# decoder_bard.net
KiCad netlist of a schematic drawn in EAGLE
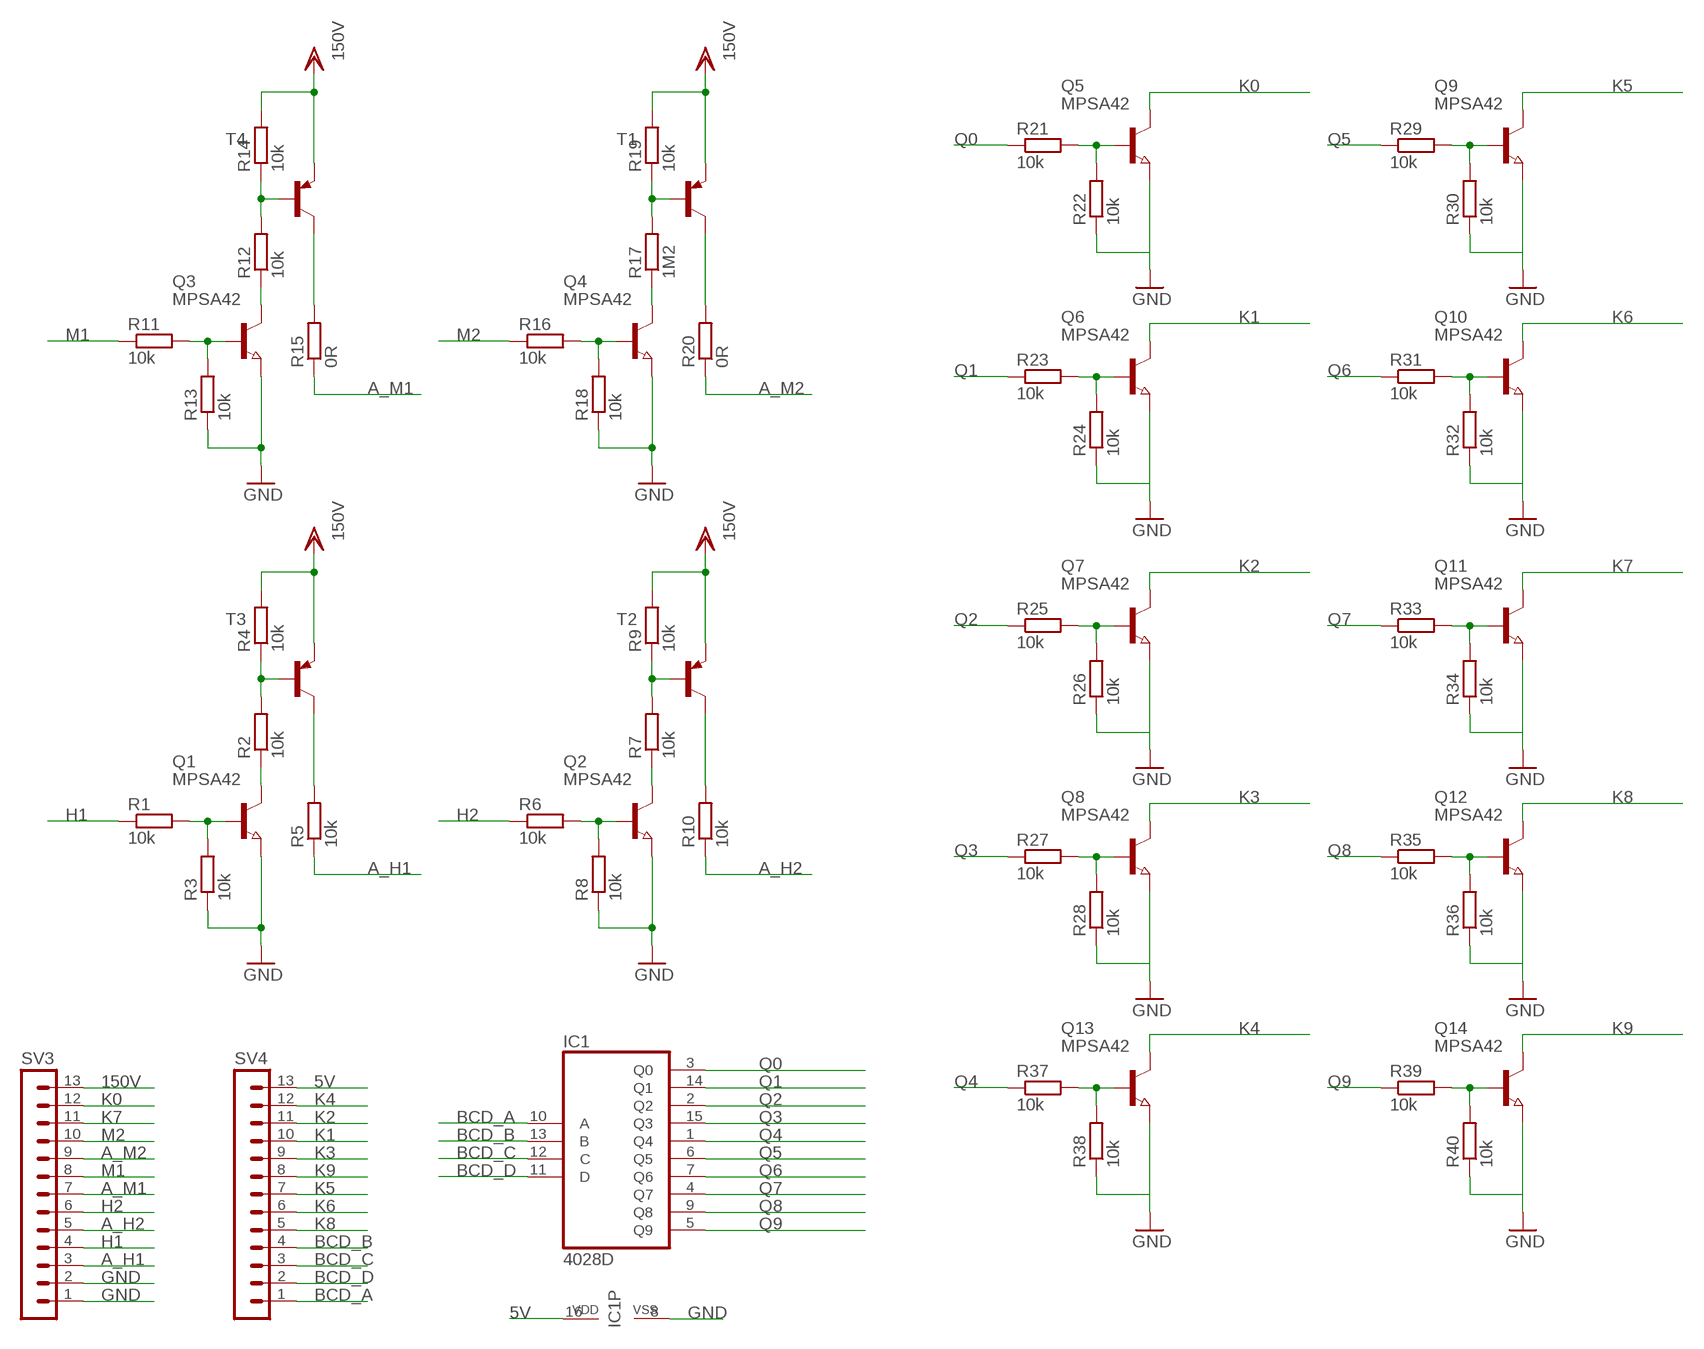
[diagram p0: schematic, sheet 1]

(export (version "E")
  (design (tool "Eeschema 10.0.6"))
  (components
    (comp (ref "IC1")
      (value "4028D")
      (footprint "eagle-import:SO16")
      (libsource (lib "eagle-import") (part "4028D"))
    )
    (comp (ref "Q1")
      (value "MPSA42")
      (footprint "eagle-import:SOT23")
      (libsource (lib "eagle-import") (part "NPN-TRANSISTOR_SOT23"))
    )
    (comp (ref "Q2")
      (value "MPSA42")
      (footprint "eagle-import:SOT23")
      (libsource (lib "eagle-import") (part "NPN-TRANSISTOR_SOT23"))
    )
    (comp (ref "Q3")
      (value "MPSA42")
      (footprint "eagle-import:SOT23")
      (libsource (lib "eagle-import") (part "NPN-TRANSISTOR_SOT23"))
    )
    (comp (ref "Q4")
      (value "MPSA42")
      (footprint "eagle-import:SOT23")
      (libsource (lib "eagle-import") (part "NPN-TRANSISTOR_SOT23"))
    )
    (comp (ref "Q5")
      (value "MPSA42")
      (footprint "eagle-import:SOT23")
      (libsource (lib "eagle-import") (part "NPN-TRANSISTOR_SOT23"))
    )
    (comp (ref "Q6")
      (value "MPSA42")
      (footprint "eagle-import:SOT23")
      (libsource (lib "eagle-import") (part "NPN-TRANSISTOR_SOT23"))
    )
    (comp (ref "Q7")
      (value "MPSA42")
      (footprint "eagle-import:SOT23")
      (libsource (lib "eagle-import") (part "NPN-TRANSISTOR_SOT23"))
    )
    (comp (ref "Q8")
      (value "MPSA42")
      (footprint "eagle-import:SOT23")
      (libsource (lib "eagle-import") (part "NPN-TRANSISTOR_SOT23"))
    )
    (comp (ref "Q9")
      (value "MPSA42")
      (footprint "eagle-import:SOT23")
      (libsource (lib "eagle-import") (part "NPN-TRANSISTOR_SOT23"))
    )
    (comp (ref "Q10")
      (value "MPSA42")
      (footprint "eagle-import:SOT23")
      (libsource (lib "eagle-import") (part "NPN-TRANSISTOR_SOT23"))
    )
    (comp (ref "Q11")
      (value "MPSA42")
      (footprint "eagle-import:SOT23")
      (libsource (lib "eagle-import") (part "NPN-TRANSISTOR_SOT23"))
    )
    (comp (ref "Q12")
      (value "MPSA42")
      (footprint "eagle-import:SOT23")
      (libsource (lib "eagle-import") (part "NPN-TRANSISTOR_SOT23"))
    )
    (comp (ref "Q13")
      (value "MPSA42")
      (footprint "eagle-import:SOT23")
      (libsource (lib "eagle-import") (part "NPN-TRANSISTOR_SOT23"))
    )
    (comp (ref "Q14")
      (value "MPSA42")
      (footprint "eagle-import:SOT23")
      (libsource (lib "eagle-import") (part "NPN-TRANSISTOR_SOT23"))
    )
    (comp (ref "R1")
      (value "10k")
      (footprint "eagle-import:R1206")
      (libsource (lib "eagle-import") (part "R-EU_R1206"))
    )
    (comp (ref "R2")
      (value "10k")
      (footprint "eagle-import:R1206")
      (libsource (lib "eagle-import") (part "R-EU_R1206"))
    )
    (comp (ref "R3")
      (value "10k")
      (footprint "eagle-import:R1206")
      (libsource (lib "eagle-import") (part "R-EU_R1206"))
    )
    (comp (ref "R4")
      (value "10k")
      (footprint "eagle-import:R1206")
      (libsource (lib "eagle-import") (part "R-EU_R1206"))
    )
    (comp (ref "R5")
      (value "10k")
      (footprint "eagle-import:R1206")
      (libsource (lib "eagle-import") (part "R-EU_R1206"))
    )
    (comp (ref "R6")
      (value "10k")
      (footprint "eagle-import:R1206")
      (libsource (lib "eagle-import") (part "R-EU_R1206"))
    )
    (comp (ref "R7")
      (value "10k")
      (footprint "eagle-import:R1206")
      (libsource (lib "eagle-import") (part "R-EU_R1206"))
    )
    (comp (ref "R8")
      (value "10k")
      (footprint "eagle-import:R1206")
      (libsource (lib "eagle-import") (part "R-EU_R1206"))
    )
    (comp (ref "R9")
      (value "10k")
      (footprint "eagle-import:R1206")
      (libsource (lib "eagle-import") (part "R-EU_R1206"))
    )
    (comp (ref "R10")
      (value "10k")
      (footprint "eagle-import:R1206")
      (libsource (lib "eagle-import") (part "R-EU_R1206"))
    )
    (comp (ref "R11")
      (value "10k")
      (footprint "eagle-import:R1206")
      (libsource (lib "eagle-import") (part "R-EU_R1206"))
    )
    (comp (ref "R12")
      (value "10k")
      (footprint "eagle-import:R1206")
      (libsource (lib "eagle-import") (part "R-EU_R1206"))
    )
    (comp (ref "R13")
      (value "10k")
      (footprint "eagle-import:R1206")
      (libsource (lib "eagle-import") (part "R-EU_R1206"))
    )
    (comp (ref "R14")
      (value "10k")
      (footprint "eagle-import:R1206")
      (libsource (lib "eagle-import") (part "R-EU_R1206"))
    )
    (comp (ref "R15")
      (value "0R")
      (footprint "eagle-import:R1206")
      (libsource (lib "eagle-import") (part "R-EU_R1206"))
    )
    (comp (ref "R16")
      (value "10k")
      (footprint "eagle-import:R1206")
      (libsource (lib "eagle-import") (part "R-EU_R1206"))
    )
    (comp (ref "R17")
      (value "1M2")
      (footprint "eagle-import:R1206")
      (libsource (lib "eagle-import") (part "R-EU_R1206"))
    )
    (comp (ref "R18")
      (value "10k")
      (footprint "eagle-import:R1206")
      (libsource (lib "eagle-import") (part "R-EU_R1206"))
    )
    (comp (ref "R19")
      (value "10k")
      (footprint "eagle-import:R1206")
      (libsource (lib "eagle-import") (part "R-EU_R1206"))
    )
    (comp (ref "R20")
      (value "0R")
      (footprint "eagle-import:R1206")
      (libsource (lib "eagle-import") (part "R-EU_R1206"))
    )
    (comp (ref "R21")
      (value "10k")
      (footprint "eagle-import:R1206")
      (libsource (lib "eagle-import") (part "R-EU_R1206"))
    )
    (comp (ref "R22")
      (value "10k")
      (footprint "eagle-import:R1206")
      (libsource (lib "eagle-import") (part "R-EU_R1206"))
    )
    (comp (ref "R23")
      (value "10k")
      (footprint "eagle-import:R1206")
      (libsource (lib "eagle-import") (part "R-EU_R1206"))
    )
    (comp (ref "R24")
      (value "10k")
      (footprint "eagle-import:R1206")
      (libsource (lib "eagle-import") (part "R-EU_R1206"))
    )
    (comp (ref "R25")
      (value "10k")
      (footprint "eagle-import:R1206")
      (libsource (lib "eagle-import") (part "R-EU_R1206"))
    )
    (comp (ref "R26")
      (value "10k")
      (footprint "eagle-import:R1206")
      (libsource (lib "eagle-import") (part "R-EU_R1206"))
    )
    (comp (ref "R27")
      (value "10k")
      (footprint "eagle-import:R1206")
      (libsource (lib "eagle-import") (part "R-EU_R1206"))
    )
    (comp (ref "R28")
      (value "10k")
      (footprint "eagle-import:R1206")
      (libsource (lib "eagle-import") (part "R-EU_R1206"))
    )
    (comp (ref "R29")
      (value "10k")
      (footprint "eagle-import:R1206")
      (libsource (lib "eagle-import") (part "R-EU_R1206"))
    )
    (comp (ref "R30")
      (value "10k")
      (footprint "eagle-import:R1206")
      (libsource (lib "eagle-import") (part "R-EU_R1206"))
    )
    (comp (ref "R31")
      (value "10k")
      (footprint "eagle-import:R1206")
      (libsource (lib "eagle-import") (part "R-EU_R1206"))
    )
    (comp (ref "R32")
      (value "10k")
      (footprint "eagle-import:R1206")
      (libsource (lib "eagle-import") (part "R-EU_R1206"))
    )
    (comp (ref "R33")
      (value "10k")
      (footprint "eagle-import:R1206")
      (libsource (lib "eagle-import") (part "R-EU_R1206"))
    )
    (comp (ref "R34")
      (value "10k")
      (footprint "eagle-import:R1206")
      (libsource (lib "eagle-import") (part "R-EU_R1206"))
    )
    (comp (ref "R35")
      (value "10k")
      (footprint "eagle-import:R1206")
      (libsource (lib "eagle-import") (part "R-EU_R1206"))
    )
    (comp (ref "R36")
      (value "10k")
      (footprint "eagle-import:R1206")
      (libsource (lib "eagle-import") (part "R-EU_R1206"))
    )
    (comp (ref "R37")
      (value "10k")
      (footprint "eagle-import:R1206")
      (libsource (lib "eagle-import") (part "R-EU_R1206"))
    )
    (comp (ref "R38")
      (value "10k")
      (footprint "eagle-import:R1206")
      (libsource (lib "eagle-import") (part "R-EU_R1206"))
    )
    (comp (ref "R39")
      (value "10k")
      (footprint "eagle-import:R1206")
      (libsource (lib "eagle-import") (part "R-EU_R1206"))
    )
    (comp (ref "R40")
      (value "10k")
      (footprint "eagle-import:R1206")
      (libsource (lib "eagle-import") (part "R-EU_R1206"))
    )
    (comp (ref "SV3")
      (value "MA13-1")
      (footprint "eagle-import:MA13-1")
      (libsource (lib "eagle-import") (part "MA13-1"))
    )
    (comp (ref "SV4")
      (value "MA13-1")
      (footprint "eagle-import:MA13-1")
      (libsource (lib "eagle-import") (part "MA13-1"))
    )
    (comp (ref "T1")
      (value "MMBTA92LT1-PNP-SOT23-BEC")
      (footprint "eagle-import:SOT23-BEC")
      (libsource (lib "eagle-import") (part "-PNP-SOT23-BECMMBTA92LT1"))
    )
    (comp (ref "T2")
      (value "MMBTA92LT1-PNP-SOT23-BEC")
      (footprint "eagle-import:SOT23-BEC")
      (libsource (lib "eagle-import") (part "-PNP-SOT23-BECMMBTA92LT1"))
    )
    (comp (ref "T3")
      (value "MMBTA92LT1-PNP-SOT23-BEC")
      (footprint "eagle-import:SOT23-BEC")
      (libsource (lib "eagle-import") (part "-PNP-SOT23-BECMMBTA92LT1"))
    )
    (comp (ref "T4")
      (value "MMBTA92LT1-PNP-SOT23-BEC")
      (footprint "eagle-import:SOT23-BEC")
      (libsource (lib "eagle-import") (part "-PNP-SOT23-BECMMBTA92LT1"))
    )
  )
  (nets
    (net (code "1") (name "/5V") (class "Default")
      (node (ref "IC1") (pin "16") (pinfunction "VDD_16") (pintype "power_in"))
      (node (ref "SV4") (pin "13") (pinfunction "13_13") (pintype "passive"))
    )
    (net (code "2") (name "/A_H1") (class "Default")
      (node (ref "R5") (pin "1") (pinfunction "1_1") (pintype "passive"))
      (node (ref "SV3") (pin "3") (pinfunction "3_3") (pintype "passive"))
    )
    (net (code "3") (name "/A_H2") (class "Default")
      (node (ref "R10") (pin "1") (pinfunction "1_1") (pintype "passive"))
      (node (ref "SV3") (pin "5") (pinfunction "5_5") (pintype "passive"))
    )
    (net (code "4") (name "/A_M1") (class "Default")
      (node (ref "R15") (pin "1") (pinfunction "1_1") (pintype "passive"))
      (node (ref "SV3") (pin "7") (pinfunction "7_7") (pintype "passive"))
    )
    (net (code "5") (name "/A_M2") (class "Default")
      (node (ref "R20") (pin "1") (pinfunction "1_1") (pintype "passive"))
      (node (ref "SV3") (pin "9") (pinfunction "9_9") (pintype "passive"))
    )
    (net (code "6") (name "/BCD_A") (class "Default")
      (node (ref "IC1") (pin "10") (pinfunction "A_10") (pintype "input"))
      (node (ref "SV4") (pin "1") (pinfunction "1_1") (pintype "passive"))
    )
    (net (code "7") (name "/BCD_B") (class "Default")
      (node (ref "IC1") (pin "13") (pinfunction "B_13") (pintype "input"))
      (node (ref "SV4") (pin "4") (pinfunction "4_4") (pintype "passive"))
    )
    (net (code "8") (name "/BCD_C") (class "Default")
      (node (ref "IC1") (pin "12") (pinfunction "C_12") (pintype "input"))
      (node (ref "SV4") (pin "3") (pinfunction "3_3") (pintype "passive"))
    )
    (net (code "9") (name "/BCD_D") (class "Default")
      (node (ref "IC1") (pin "11") (pinfunction "D_11") (pintype "input"))
      (node (ref "SV4") (pin "2") (pinfunction "2_2") (pintype "passive"))
    )
    (net (code "10") (name "/H1") (class "Default")
      (node (ref "R1") (pin "1") (pinfunction "1_1") (pintype "passive"))
      (node (ref "SV3") (pin "4") (pinfunction "4_4") (pintype "passive"))
    )
    (net (code "11") (name "/H2") (class "Default")
      (node (ref "R6") (pin "1") (pinfunction "1_1") (pintype "passive"))
      (node (ref "SV3") (pin "6") (pinfunction "6_6") (pintype "passive"))
    )
    (net (code "12") (name "/K0") (class "Default")
      (node (ref "Q5") (pin "3") (pinfunction "C_3") (pintype "passive"))
      (node (ref "SV3") (pin "12") (pinfunction "12_12") (pintype "passive"))
    )
    (net (code "13") (name "/K1") (class "Default")
      (node (ref "Q6") (pin "3") (pinfunction "C_3") (pintype "passive"))
      (node (ref "SV4") (pin "10") (pinfunction "10_10") (pintype "passive"))
    )
    (net (code "14") (name "/K2") (class "Default")
      (node (ref "Q7") (pin "3") (pinfunction "C_3") (pintype "passive"))
      (node (ref "SV4") (pin "11") (pinfunction "11_11") (pintype "passive"))
    )
    (net (code "15") (name "/K3") (class "Default")
      (node (ref "Q8") (pin "3") (pinfunction "C_3") (pintype "passive"))
      (node (ref "SV4") (pin "9") (pinfunction "9_9") (pintype "passive"))
    )
    (net (code "16") (name "/K4") (class "Default")
      (node (ref "Q13") (pin "3") (pinfunction "C_3") (pintype "passive"))
      (node (ref "SV4") (pin "12") (pinfunction "12_12") (pintype "passive"))
    )
    (net (code "17") (name "/K5") (class "Default")
      (node (ref "Q9") (pin "3") (pinfunction "C_3") (pintype "passive"))
      (node (ref "SV4") (pin "7") (pinfunction "7_7") (pintype "passive"))
    )
    (net (code "18") (name "/K6") (class "Default")
      (node (ref "Q10") (pin "3") (pinfunction "C_3") (pintype "passive"))
      (node (ref "SV4") (pin "6") (pinfunction "6_6") (pintype "passive"))
    )
    (net (code "19") (name "/K7") (class "Default")
      (node (ref "Q11") (pin "3") (pinfunction "C_3") (pintype "passive"))
      (node (ref "SV3") (pin "11") (pinfunction "11_11") (pintype "passive"))
    )
    (net (code "20") (name "/K8") (class "Default")
      (node (ref "Q12") (pin "3") (pinfunction "C_3") (pintype "passive"))
      (node (ref "SV4") (pin "5") (pinfunction "5_5") (pintype "passive"))
    )
    (net (code "21") (name "/K9") (class "Default")
      (node (ref "Q14") (pin "3") (pinfunction "C_3") (pintype "passive"))
      (node (ref "SV4") (pin "8") (pinfunction "8_8") (pintype "passive"))
    )
    (net (code "22") (name "/M1") (class "Default")
      (node (ref "R11") (pin "1") (pinfunction "1_1") (pintype "passive"))
      (node (ref "SV3") (pin "8") (pinfunction "8_8") (pintype "passive"))
    )
    (net (code "23") (name "/M2") (class "Default")
      (node (ref "R16") (pin "1") (pinfunction "1_1") (pintype "passive"))
      (node (ref "SV3") (pin "10") (pinfunction "10_10") (pintype "passive"))
    )
    (net (code "24") (name "/Q0") (class "Default")
      (node (ref "IC1") (pin "3") (pinfunction "Q0_3") (pintype "output"))
      (node (ref "R21") (pin "1") (pinfunction "1_1") (pintype "passive"))
    )
    (net (code "25") (name "/Q1") (class "Default")
      (node (ref "IC1") (pin "14") (pinfunction "Q1_14") (pintype "output"))
      (node (ref "R23") (pin "1") (pinfunction "1_1") (pintype "passive"))
    )
    (net (code "26") (name "/Q2") (class "Default")
      (node (ref "IC1") (pin "2") (pinfunction "Q2_2") (pintype "output"))
      (node (ref "R25") (pin "1") (pinfunction "1_1") (pintype "passive"))
    )
    (net (code "27") (name "/Q3") (class "Default")
      (node (ref "IC1") (pin "15") (pinfunction "Q3_15") (pintype "output"))
      (node (ref "R27") (pin "1") (pinfunction "1_1") (pintype "passive"))
    )
    (net (code "28") (name "/Q4") (class "Default")
      (node (ref "IC1") (pin "1") (pinfunction "Q4_1") (pintype "output"))
      (node (ref "R37") (pin "1") (pinfunction "1_1") (pintype "passive"))
    )
    (net (code "29") (name "/Q5") (class "Default")
      (node (ref "IC1") (pin "6") (pinfunction "Q5_6") (pintype "output"))
      (node (ref "R29") (pin "1") (pinfunction "1_1") (pintype "passive"))
    )
    (net (code "30") (name "/Q6") (class "Default")
      (node (ref "IC1") (pin "7") (pinfunction "Q6_7") (pintype "output"))
      (node (ref "R31") (pin "1") (pinfunction "1_1") (pintype "passive"))
    )
    (net (code "31") (name "/Q7") (class "Default")
      (node (ref "IC1") (pin "4") (pinfunction "Q7_4") (pintype "output"))
      (node (ref "R33") (pin "1") (pinfunction "1_1") (pintype "passive"))
    )
    (net (code "32") (name "/Q8") (class "Default")
      (node (ref "IC1") (pin "9") (pinfunction "Q8_9") (pintype "output"))
      (node (ref "R35") (pin "1") (pinfunction "1_1") (pintype "passive"))
    )
    (net (code "33") (name "/Q9") (class "Default")
      (node (ref "IC1") (pin "5") (pinfunction "Q9_5") (pintype "output"))
      (node (ref "R39") (pin "1") (pinfunction "1_1") (pintype "passive"))
    )
    (net (code "34") (name "150V") (class "Default")
      (node (ref "R14") (pin "2") (pinfunction "2_2") (pintype "passive"))
      (node (ref "R19") (pin "2") (pinfunction "2_2") (pintype "passive"))
      (node (ref "R4") (pin "2") (pinfunction "2_2") (pintype "passive"))
      (node (ref "R9") (pin "2") (pinfunction "2_2") (pintype "passive"))
      (node (ref "SV3") (pin "13") (pinfunction "13_13") (pintype "passive"))
      (node (ref "T1") (pin "E") (pinfunction "E_E") (pintype "passive"))
      (node (ref "T2") (pin "E") (pinfunction "E_E") (pintype "passive"))
      (node (ref "T3") (pin "E") (pinfunction "E_E") (pintype "passive"))
      (node (ref "T4") (pin "E") (pinfunction "E_E") (pintype "passive"))
    )
    (net (code "35") (name "GND") (class "Default")
      (node (ref "IC1") (pin "8") (pinfunction "VSS_8") (pintype "power_in"))
      (node (ref "Q1") (pin "2") (pinfunction "E_2") (pintype "passive"))
      (node (ref "Q10") (pin "2") (pinfunction "E_2") (pintype "passive"))
      (node (ref "Q11") (pin "2") (pinfunction "E_2") (pintype "passive"))
      (node (ref "Q12") (pin "2") (pinfunction "E_2") (pintype "passive"))
      (node (ref "Q13") (pin "2") (pinfunction "E_2") (pintype "passive"))
      (node (ref "Q14") (pin "2") (pinfunction "E_2") (pintype "passive"))
      (node (ref "Q2") (pin "2") (pinfunction "E_2") (pintype "passive"))
      (node (ref "Q3") (pin "2") (pinfunction "E_2") (pintype "passive"))
      (node (ref "Q4") (pin "2") (pinfunction "E_2") (pintype "passive"))
      (node (ref "Q5") (pin "2") (pinfunction "E_2") (pintype "passive"))
      (node (ref "Q6") (pin "2") (pinfunction "E_2") (pintype "passive"))
      (node (ref "Q7") (pin "2") (pinfunction "E_2") (pintype "passive"))
      (node (ref "Q8") (pin "2") (pinfunction "E_2") (pintype "passive"))
      (node (ref "Q9") (pin "2") (pinfunction "E_2") (pintype "passive"))
      (node (ref "R13") (pin "1") (pinfunction "1_1") (pintype "passive"))
      (node (ref "R18") (pin "1") (pinfunction "1_1") (pintype "passive"))
      (node (ref "R22") (pin "1") (pinfunction "1_1") (pintype "passive"))
      (node (ref "R24") (pin "1") (pinfunction "1_1") (pintype "passive"))
      (node (ref "R26") (pin "1") (pinfunction "1_1") (pintype "passive"))
      (node (ref "R28") (pin "1") (pinfunction "1_1") (pintype "passive"))
      (node (ref "R3") (pin "1") (pinfunction "1_1") (pintype "passive"))
      (node (ref "R30") (pin "1") (pinfunction "1_1") (pintype "passive"))
      (node (ref "R32") (pin "1") (pinfunction "1_1") (pintype "passive"))
      (node (ref "R34") (pin "1") (pinfunction "1_1") (pintype "passive"))
      (node (ref "R36") (pin "1") (pinfunction "1_1") (pintype "passive"))
      (node (ref "R38") (pin "1") (pinfunction "1_1") (pintype "passive"))
      (node (ref "R40") (pin "1") (pinfunction "1_1") (pintype "passive"))
      (node (ref "R8") (pin "1") (pinfunction "1_1") (pintype "passive"))
      (node (ref "SV3") (pin "1") (pinfunction "1_1") (pintype "passive"))
      (node (ref "SV3") (pin "2") (pinfunction "2_2") (pintype "passive"))
    )
    (net (code "36") (name "Net-(Q1-B)") (class "Default")
      (node (ref "Q1") (pin "1") (pinfunction "B_1") (pintype "passive"))
      (node (ref "R1") (pin "2") (pinfunction "2_2") (pintype "passive"))
      (node (ref "R3") (pin "2") (pinfunction "2_2") (pintype "passive"))
    )
    (net (code "37") (name "Net-(Q1-C)") (class "Default")
      (node (ref "Q1") (pin "3") (pinfunction "C_3") (pintype "passive"))
      (node (ref "R2") (pin "1") (pinfunction "1_1") (pintype "passive"))
    )
    (net (code "38") (name "Net-(Q2-B)") (class "Default")
      (node (ref "Q2") (pin "1") (pinfunction "B_1") (pintype "passive"))
      (node (ref "R6") (pin "2") (pinfunction "2_2") (pintype "passive"))
      (node (ref "R8") (pin "2") (pinfunction "2_2") (pintype "passive"))
    )
    (net (code "39") (name "Net-(Q2-C)") (class "Default")
      (node (ref "Q2") (pin "3") (pinfunction "C_3") (pintype "passive"))
      (node (ref "R7") (pin "1") (pinfunction "1_1") (pintype "passive"))
    )
    (net (code "40") (name "Net-(Q3-B)") (class "Default")
      (node (ref "Q3") (pin "1") (pinfunction "B_1") (pintype "passive"))
      (node (ref "R11") (pin "2") (pinfunction "2_2") (pintype "passive"))
      (node (ref "R13") (pin "2") (pinfunction "2_2") (pintype "passive"))
    )
    (net (code "41") (name "Net-(Q3-C)") (class "Default")
      (node (ref "Q3") (pin "3") (pinfunction "C_3") (pintype "passive"))
      (node (ref "R12") (pin "1") (pinfunction "1_1") (pintype "passive"))
    )
    (net (code "42") (name "Net-(Q4-B)") (class "Default")
      (node (ref "Q4") (pin "1") (pinfunction "B_1") (pintype "passive"))
      (node (ref "R16") (pin "2") (pinfunction "2_2") (pintype "passive"))
      (node (ref "R18") (pin "2") (pinfunction "2_2") (pintype "passive"))
    )
    (net (code "43") (name "Net-(Q4-C)") (class "Default")
      (node (ref "Q4") (pin "3") (pinfunction "C_3") (pintype "passive"))
      (node (ref "R17") (pin "1") (pinfunction "1_1") (pintype "passive"))
    )
    (net (code "44") (name "Net-(Q5-B)") (class "Default")
      (node (ref "Q5") (pin "1") (pinfunction "B_1") (pintype "passive"))
      (node (ref "R21") (pin "2") (pinfunction "2_2") (pintype "passive"))
      (node (ref "R22") (pin "2") (pinfunction "2_2") (pintype "passive"))
    )
    (net (code "45") (name "Net-(Q6-B)") (class "Default")
      (node (ref "Q6") (pin "1") (pinfunction "B_1") (pintype "passive"))
      (node (ref "R23") (pin "2") (pinfunction "2_2") (pintype "passive"))
      (node (ref "R24") (pin "2") (pinfunction "2_2") (pintype "passive"))
    )
    (net (code "46") (name "Net-(Q7-B)") (class "Default")
      (node (ref "Q7") (pin "1") (pinfunction "B_1") (pintype "passive"))
      (node (ref "R25") (pin "2") (pinfunction "2_2") (pintype "passive"))
      (node (ref "R26") (pin "2") (pinfunction "2_2") (pintype "passive"))
    )
    (net (code "47") (name "Net-(Q8-B)") (class "Default")
      (node (ref "Q8") (pin "1") (pinfunction "B_1") (pintype "passive"))
      (node (ref "R27") (pin "2") (pinfunction "2_2") (pintype "passive"))
      (node (ref "R28") (pin "2") (pinfunction "2_2") (pintype "passive"))
    )
    (net (code "48") (name "Net-(Q9-B)") (class "Default")
      (node (ref "Q9") (pin "1") (pinfunction "B_1") (pintype "passive"))
      (node (ref "R29") (pin "2") (pinfunction "2_2") (pintype "passive"))
      (node (ref "R30") (pin "2") (pinfunction "2_2") (pintype "passive"))
    )
    (net (code "49") (name "Net-(Q10-B)") (class "Default")
      (node (ref "Q10") (pin "1") (pinfunction "B_1") (pintype "passive"))
      (node (ref "R31") (pin "2") (pinfunction "2_2") (pintype "passive"))
      (node (ref "R32") (pin "2") (pinfunction "2_2") (pintype "passive"))
    )
    (net (code "50") (name "Net-(Q11-B)") (class "Default")
      (node (ref "Q11") (pin "1") (pinfunction "B_1") (pintype "passive"))
      (node (ref "R33") (pin "2") (pinfunction "2_2") (pintype "passive"))
      (node (ref "R34") (pin "2") (pinfunction "2_2") (pintype "passive"))
    )
    (net (code "51") (name "Net-(Q12-B)") (class "Default")
      (node (ref "Q12") (pin "1") (pinfunction "B_1") (pintype "passive"))
      (node (ref "R35") (pin "2") (pinfunction "2_2") (pintype "passive"))
      (node (ref "R36") (pin "2") (pinfunction "2_2") (pintype "passive"))
    )
    (net (code "52") (name "Net-(Q13-B)") (class "Default")
      (node (ref "Q13") (pin "1") (pinfunction "B_1") (pintype "passive"))
      (node (ref "R37") (pin "2") (pinfunction "2_2") (pintype "passive"))
      (node (ref "R38") (pin "2") (pinfunction "2_2") (pintype "passive"))
    )
    (net (code "53") (name "Net-(Q14-B)") (class "Default")
      (node (ref "Q14") (pin "1") (pinfunction "B_1") (pintype "passive"))
      (node (ref "R39") (pin "2") (pinfunction "2_2") (pintype "passive"))
      (node (ref "R40") (pin "2") (pinfunction "2_2") (pintype "passive"))
    )
    (net (code "54") (name "Net-(R2-Pad2)") (class "Default")
      (node (ref "R2") (pin "2") (pinfunction "2_2") (pintype "passive"))
      (node (ref "R4") (pin "1") (pinfunction "1_1") (pintype "passive"))
      (node (ref "T3") (pin "B") (pinfunction "B_B") (pintype "passive"))
    )
    (net (code "55") (name "Net-(R5-Pad2)") (class "Default")
      (node (ref "R5") (pin "2") (pinfunction "2_2") (pintype "passive"))
      (node (ref "T3") (pin "C") (pinfunction "C_C") (pintype "passive"))
    )
    (net (code "56") (name "Net-(R7-Pad2)") (class "Default")
      (node (ref "R7") (pin "2") (pinfunction "2_2") (pintype "passive"))
      (node (ref "R9") (pin "1") (pinfunction "1_1") (pintype "passive"))
      (node (ref "T2") (pin "B") (pinfunction "B_B") (pintype "passive"))
    )
    (net (code "57") (name "Net-(R10-Pad2)") (class "Default")
      (node (ref "R10") (pin "2") (pinfunction "2_2") (pintype "passive"))
      (node (ref "T2") (pin "C") (pinfunction "C_C") (pintype "passive"))
    )
    (net (code "58") (name "Net-(R12-Pad2)") (class "Default")
      (node (ref "R12") (pin "2") (pinfunction "2_2") (pintype "passive"))
      (node (ref "R14") (pin "1") (pinfunction "1_1") (pintype "passive"))
      (node (ref "T4") (pin "B") (pinfunction "B_B") (pintype "passive"))
    )
    (net (code "59") (name "Net-(R15-Pad2)") (class "Default")
      (node (ref "R15") (pin "2") (pinfunction "2_2") (pintype "passive"))
      (node (ref "T4") (pin "C") (pinfunction "C_C") (pintype "passive"))
    )
    (net (code "60") (name "Net-(R17-Pad2)") (class "Default")
      (node (ref "R17") (pin "2") (pinfunction "2_2") (pintype "passive"))
      (node (ref "R19") (pin "1") (pinfunction "1_1") (pintype "passive"))
      (node (ref "T1") (pin "B") (pinfunction "B_B") (pintype "passive"))
    )
    (net (code "61") (name "Net-(R20-Pad2)") (class "Default")
      (node (ref "R20") (pin "2") (pinfunction "2_2") (pintype "passive"))
      (node (ref "T1") (pin "C") (pinfunction "C_C") (pintype "passive"))
    )
  )
)
